# Driver_SW.net
KiCad netlist of a schematic drawn in Altium Designer
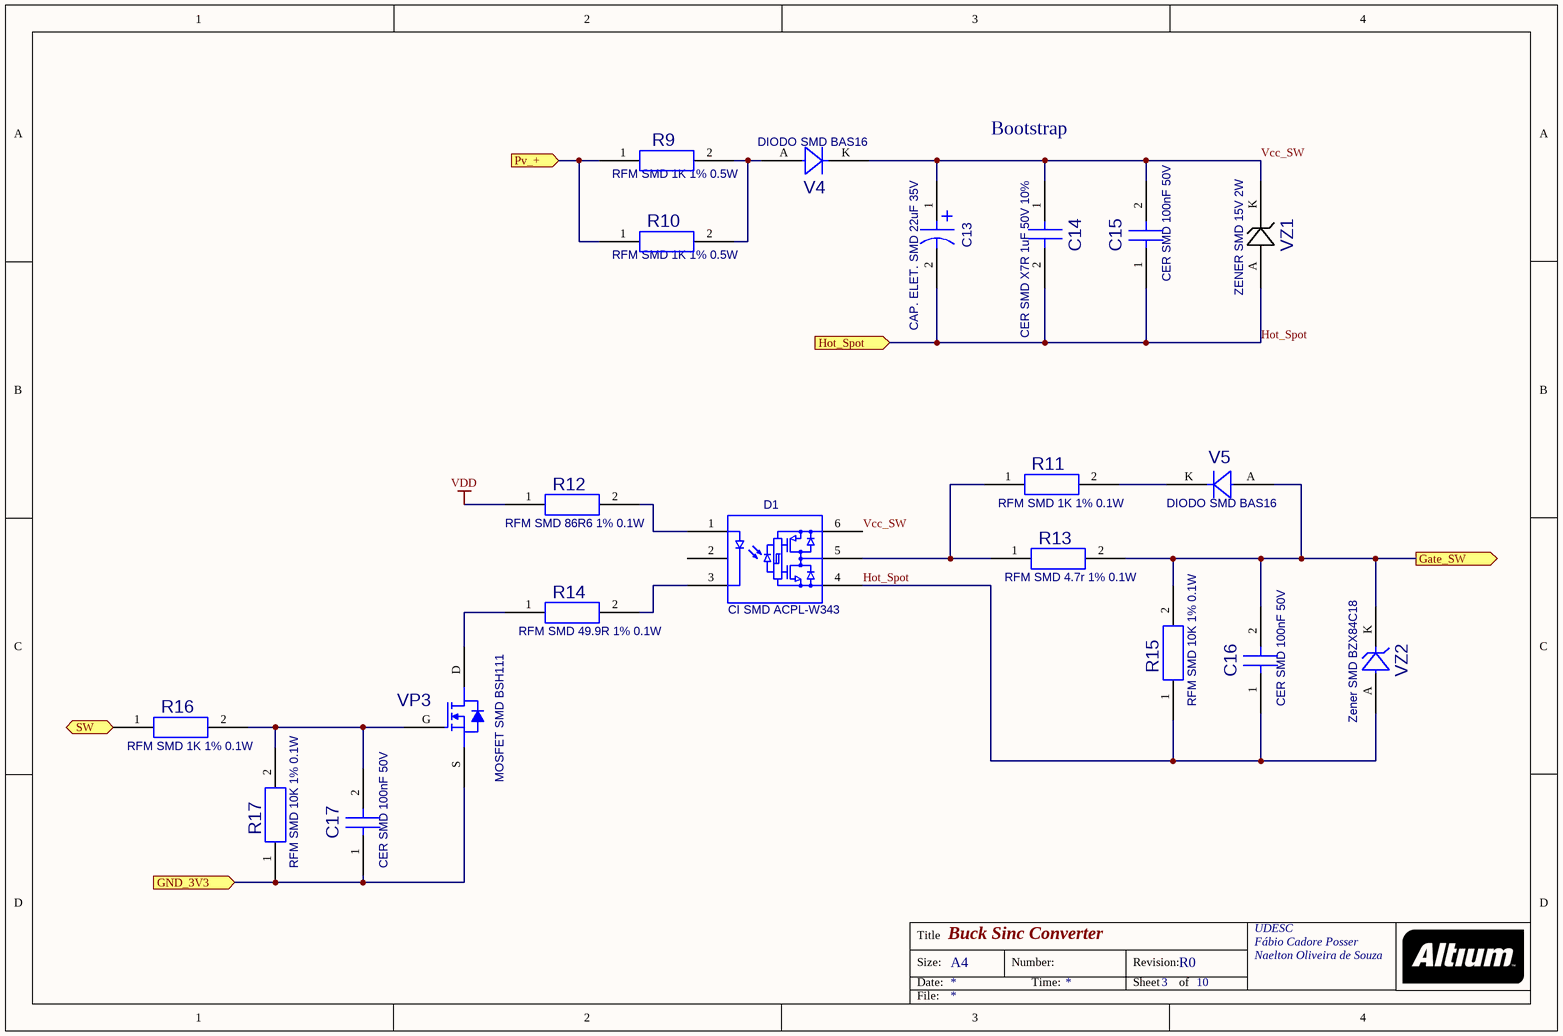
[diagram p0: Driver_SW.SchDoc]

(export (version "E")
  (design (tool "Eeschema 10.0.6"))
  (components
    (comp (ref "C13")
      (value "CAP. ELET. SMD 22uF 35V")
      (footprint "CAP UUD CR 5X5.8")
      (fields (field (name "Comment") "11690909"))
      (libsource (lib "Buck_Converter") (part "11690909"))
    )
    (comp (ref "C14")
      (value "CER SMD X7R 1uF 50V 10%")
      (footprint "C0805_R_V0")
      (fields (field (name "Comment") "11736520"))
      (libsource (lib "Buck_Converter") (part "11736520"))
    )
    (comp (ref "C15")
      (value "CER SMD 100nF 50V")
      (footprint "C0805_R_V0")
      (fields (field (name "Comment") "10192075"))
      (libsource (lib "Buck_Converter") (part "10192075"))
    )
    (comp (ref "C16")
      (value "CER SMD 100nF 50V")
      (footprint "C0805_R_V0")
      (fields (field (name "Comment") "10192075"))
      (libsource (lib "Buck_Converter") (part "10192075"))
    )
    (comp (ref "C17")
      (value "CER SMD 100nF 50V")
      (footprint "C0805_R_V0")
      (fields (field (name "Comment") "10192075"))
      (libsource (lib "Buck_Converter") (part "10192075"))
    )
    (comp (ref "D1")
      (value "CI SMD ACPL-W343")
      (footprint "SO-6 (11.5 MM)")
      (fields (field (name "Comment") "12544475"))
      (libsource (lib "Buck_Converter") (part "12544475"))
    )
    (comp (ref "R9")
      (value "RFM SMD 1K 1% 0.5W")
      (footprint "R2010A")
      (fields (field (name "Comment") "10191999"))
      (libsource (lib "Buck_Converter") (part "10191999"))
    )
    (comp (ref "R10")
      (value "RFM SMD 1K 1% 0.5W")
      (footprint "R2010A")
      (fields (field (name "Comment") "10191999"))
      (libsource (lib "Buck_Converter") (part "10191999"))
    )
    (comp (ref "R11")
      (value "RFM SMD 1K 1% 0.1W")
      (footprint "R0805_R_V0")
      (fields (field (name "Comment") "10118077"))
      (libsource (lib "Buck_Converter") (part "10118077"))
    )
    (comp (ref "R12")
      (value "RFM SMD 86R6 1% 0.1W")
      (footprint "R0805_R_V0")
      (fields (field (name "Comment") "10192050"))
      (libsource (lib "Buck_Converter") (part "10118077"))
    )
    (comp (ref "R13")
      (value "RFM SMD 4.7r 1% 0.1W")
      (footprint "R0805_R_V0")
      (fields (field (name "Comment") "10192015"))
      (libsource (lib "Buck_Converter") (part "10118077"))
    )
    (comp (ref "R14")
      (value "RFM SMD 49.9R 1% 0.1W")
      (footprint "R0805_R_V0")
      (fields (field (name "Comment") "10192035"))
      (libsource (lib "Buck_Converter") (part "10118077"))
    )
    (comp (ref "R15")
      (value "RFM SMD 10K 1% 0.1W")
      (footprint "R0805_R_V0")
      (fields (field (name "Comment") "10118076"))
      (libsource (lib "Buck_Converter") (part "10118077"))
    )
    (comp (ref "R16")
      (value "RFM SMD 1K 1% 0.1W")
      (footprint "R0805_R_V0")
      (fields (field (name "Comment") "10118077"))
      (libsource (lib "Buck_Converter") (part "10118077"))
    )
    (comp (ref "R17")
      (value "RFM SMD 10K 1% 0.1W")
      (footprint "R0805_R_V0")
      (fields (field (name "Comment") "10118076"))
      (libsource (lib "Buck_Converter") (part "10118077"))
    )
    (comp (ref "V4")
      (value "DIODO SMD BAS16")
      (footprint "SOT23A")
      (fields (field (name "Comment") "10261302"))
      (libsource (lib "Buck_Converter") (part "10261302"))
    )
    (comp (ref "V5")
      (value "DIODO SMD BAS16")
      (footprint "SOT23A")
      (fields (field (name "Comment") "10261302"))
      (libsource (lib "Buck_Converter") (part "10261302"))
    )
    (comp (ref "VP3")
      (value "MOSFET SMD BSH111")
      (footprint "MOS_SOT23A")
      (fields (field (name "Comment") "11110327"))
      (libsource (lib "Buck_Converter") (part "11110327"))
    )
    (comp (ref "VZ1")
      (value "ZENER SMD 15V 2W")
      (footprint "DO-214AC_12665621(Primary)")
      (fields (field (name "Comment") "12665621"))
      (libsource (lib "Buck_converter") (part "12665621"))
    )
    (comp (ref "VZ2")
      (value "Zener SMD BZX84C18")
      (footprint "ZEN_SOT23A")
      (description "Zener  SMD BZX84C18")
      (fields (field (name "Comment") "10050447"))
      (libsource (lib "Buck_Converter") (part "10050447"))
    )
  )
  (nets
    (net (code "1") (name "/GND_3V3") (class "Default")
      (node (ref "C17") (pin "1") (pinfunction "1_1") (pintype "passive"))
      (node (ref "R17") (pin "1") (pinfunction "1_1") (pintype "passive"))
      (node (ref "VP3") (pin "S") (pinfunction "S_S") (pintype "passive"))
    )
    (net (code "2") (name "/Gate_SW") (class "Default")
      (node (ref "C16") (pin "2") (pinfunction "2_2") (pintype "passive"))
      (node (ref "R13") (pin "2") (pinfunction "2_2") (pintype "passive"))
      (node (ref "R15") (pin "2") (pinfunction "2_2") (pintype "passive"))
      (node (ref "V5") (pin "A") (pinfunction "A_A") (pintype "passive"))
      (node (ref "VZ2") (pin "K") (pinfunction "K_K") (pintype "passive"))
    )
    (net (code "3") (name "/Hot_Spot") (class "Default")
      (node (ref "C13") (pin "2") (pinfunction "2_2") (pintype "passive"))
      (node (ref "C14") (pin "2") (pinfunction "2_2") (pintype "passive"))
      (node (ref "C15") (pin "1") (pinfunction "1_1") (pintype "passive"))
      (node (ref "C16") (pin "1") (pinfunction "1_1") (pintype "passive"))
      (node (ref "D1") (pin "4") (pinfunction "VEE_4") (pintype "passive"))
      (node (ref "R15") (pin "1") (pinfunction "1_1") (pintype "passive"))
      (node (ref "VZ1") (pin "A") (pinfunction "A_A") (pintype "passive"))
      (node (ref "VZ2") (pin "A") (pinfunction "A_A") (pintype "passive"))
    )
    (net (code "4") (name "/Pv_+") (class "Default")
      (node (ref "R10") (pin "1") (pinfunction "1_1") (pintype "passive"))
      (node (ref "R9") (pin "1") (pinfunction "1_1") (pintype "passive"))
    )
    (net (code "5") (name "/SW") (class "Default")
      (node (ref "R16") (pin "1") (pinfunction "1_1") (pintype "passive"))
    )
    (net (code "6") (name "/Vcc_SW") (class "Default")
      (node (ref "C13") (pin "1") (pinfunction "1_1") (pintype "passive"))
      (node (ref "C14") (pin "1") (pinfunction "1_1") (pintype "passive"))
      (node (ref "C15") (pin "2") (pinfunction "2_2") (pintype "passive"))
      (node (ref "D1") (pin "6") (pinfunction "VCC_6") (pintype "passive"))
      (node (ref "V4") (pin "K") (pinfunction "K_K") (pintype "passive"))
      (node (ref "VZ1") (pin "K") (pinfunction "K_K") (pintype "passive"))
    )
    (net (code "7") (name "Net-(C17-Pad2)") (class "Default")
      (node (ref "C17") (pin "2") (pinfunction "2_2") (pintype "passive"))
      (node (ref "R16") (pin "2") (pinfunction "2_2") (pintype "passive"))
      (node (ref "R17") (pin "2") (pinfunction "2_2") (pintype "passive"))
      (node (ref "VP3") (pin "G") (pinfunction "G_G") (pintype "passive"))
    )
    (net (code "8") (name "Net-(D1-A)") (class "Default")
      (node (ref "D1") (pin "1") (pinfunction "A_1") (pintype "passive"))
      (node (ref "R12") (pin "2") (pinfunction "2_2") (pintype "passive"))
    )
    (net (code "9") (name "Net-(D1-K)") (class "Default")
      (node (ref "D1") (pin "3") (pinfunction "K_3") (pintype "passive"))
      (node (ref "R14") (pin "2") (pinfunction "2_2") (pintype "passive"))
    )
    (net (code "10") (name "Net-(D1-VOUT)") (class "Default")
      (node (ref "D1") (pin "5") (pinfunction "VOUT_5") (pintype "passive"))
      (node (ref "R11") (pin "1") (pinfunction "1_1") (pintype "passive"))
      (node (ref "R13") (pin "1") (pinfunction "1_1") (pintype "passive"))
    )
    (net (code "11") (name "Net-(R10-Pad2)") (class "Default")
      (node (ref "R10") (pin "2") (pinfunction "2_2") (pintype "passive"))
      (node (ref "R9") (pin "2") (pinfunction "2_2") (pintype "passive"))
      (node (ref "V4") (pin "A") (pinfunction "A_A") (pintype "passive"))
    )
    (net (code "12") (name "Net-(R11-Pad2)") (class "Default")
      (node (ref "R11") (pin "2") (pinfunction "2_2") (pintype "passive"))
      (node (ref "V5") (pin "K") (pinfunction "K_K") (pintype "passive"))
    )
    (net (code "13") (name "Net-(R14-Pad1)") (class "Default")
      (node (ref "R14") (pin "1") (pinfunction "1_1") (pintype "passive"))
      (node (ref "VP3") (pin "D") (pinfunction "D_D") (pintype "passive"))
    )
    (net (code "14") (name "VDD") (class "Default")
      (node (ref "R12") (pin "1") (pinfunction "1_1") (pintype "passive"))
    )
    (net (code "15") (name "unconnected-(D1-Pad2)") (class "Default")
      (node (ref "D1") (pin "2") (pinfunction "2_2") (pintype "passive"))
    )
    (net (code "16") (name "unconnected-(V4-PadNC)") (class "Default")
      (node (ref "V4") (pin "NC") (pintype "passive"))
    )
    (net (code "17") (name "unconnected-(V5-PadNC)") (class "Default")
      (node (ref "V5") (pin "NC") (pintype "passive"))
    )
    (net (code "18") (name "unconnected-(VZ2-PadNC)") (class "Default")
      (node (ref "VZ2") (pin "NC") (pintype "passive"))
    )
  )
)
